# JacdacServoDual_23.net
KiCad netlist of a schematic drawn in Altium Designer
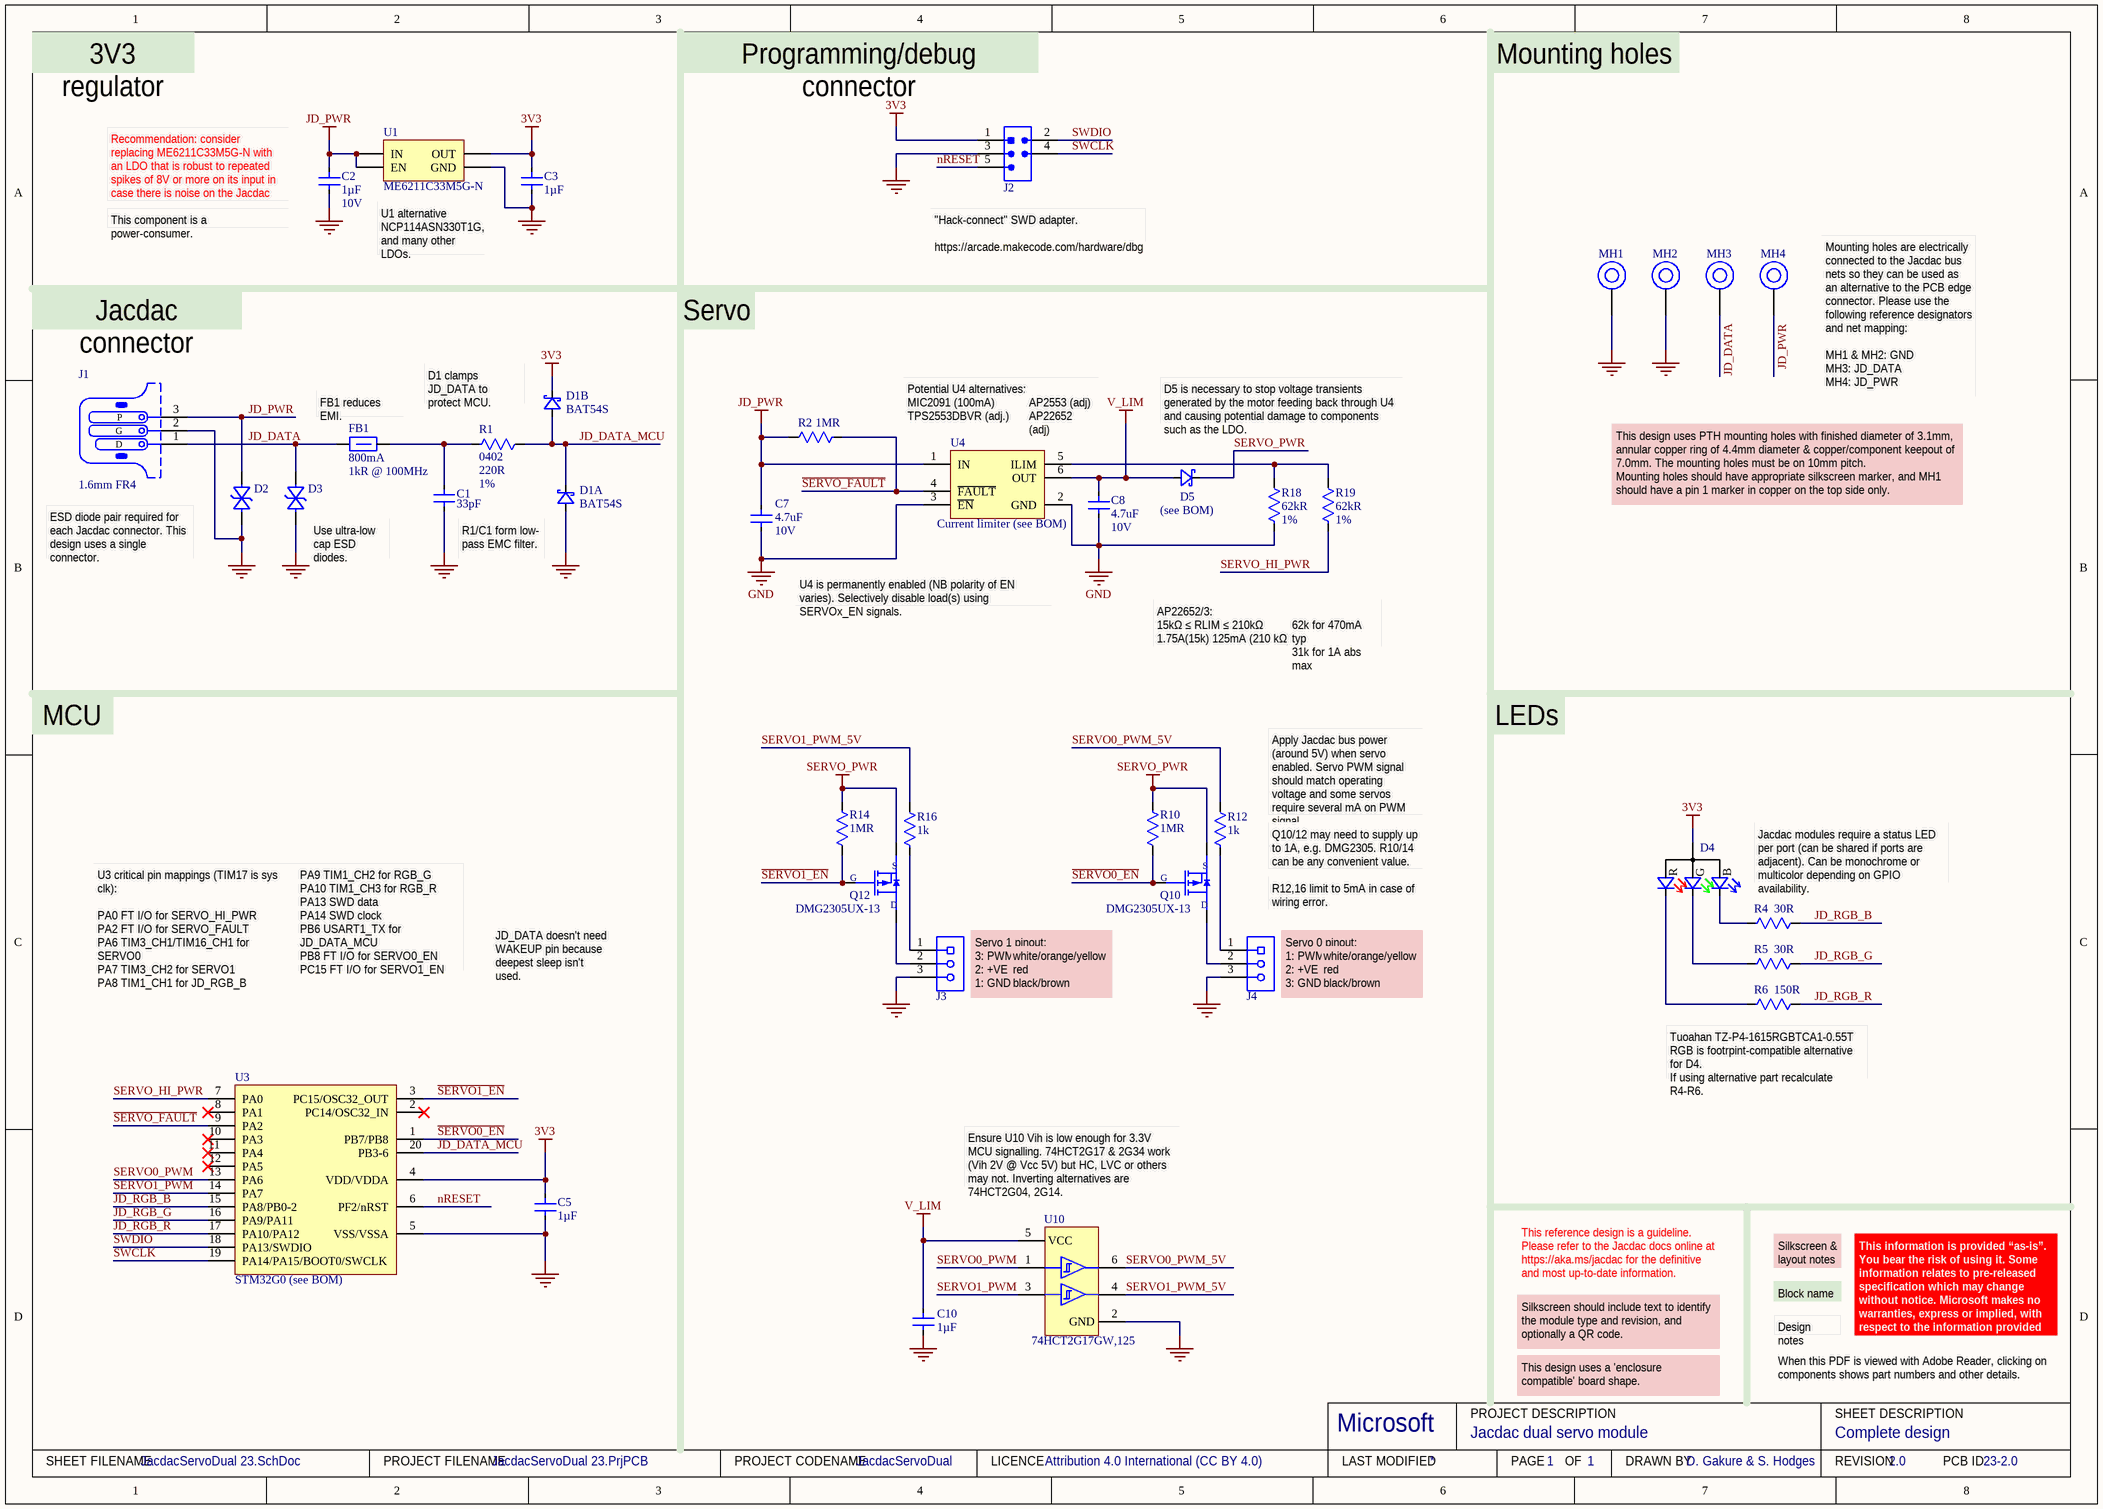
[diagram p0: JacdacServoDual 23.SchDoc]

(export (version "E")
  (design (tool "Eeschema 10.0.6"))
  (components
    (comp (ref "C1")
      (value "CL05C330JB5NNNC")
      (footprint "C0402_0.55MM - without outline")
      (description "CAP CER 33PF 50V C0G/NP0 0402")
      (fields
        (field (name "MANUFACTURER") "Samsung")
        (field (name "TOLERANCE") "5%")
        (field (name "CAPACITANCE") "33pF")
      )
      (libsource (lib "Samsung") (part "CL05C330JB5NNNC"))
    )
    (comp (ref "C2")
      (value "CL05A105KP5NNNC")
      (footprint "C0402_0.55MM - without outline")
      (description "CAP CER 1UF 10V X5R 0402")
      (fields
        (field (name "MANUFACTURER") "Samsung")
        (field (name "TOLERANCE") "10%")
        (field (name "CAPACITANCE") "1µF")
        (field (name "VOLTAGE RATING") "10V")
        (field (name "CREATED") "DG")
        (field (name "CHECKED") "?")
      )
      (libsource (lib "Samsung") (part "CL05A105KP5NNNC"))
    )
    (comp (ref "C3")
      (value "CL05A105KP5NNNC")
      (footprint "C0402_0.55MM - without outline")
      (description "CAP CER 1UF 10V X5R 0402")
      (fields
        (field (name "MANUFACTURER") "Samsung")
        (field (name "TOLERANCE") "10%")
        (field (name "CAPACITANCE") "1µF")
        (field (name "CREATED") "DG")
        (field (name "CHECKED") "?")
      )
      (libsource (lib "Samsung") (part "CL05A105KP5NNNC"))
    )
    (comp (ref "C5")
      (value "CL05A105KP5NNNC")
      (footprint "C0402_0.55MM - without outline")
      (description "CAP CER 1UF 10V X5R 0402")
      (fields
        (field (name "MANUFACTURER") "Samsung")
        (field (name "TOLERANCE") "10%")
        (field (name "CAPACITANCE") "1µF")
        (field (name "CREATED") "DG")
        (field (name "CHECKED") "?")
      )
      (libsource (lib "Samsung") (part "CL05A105KP5NNNC"))
    )
    (comp (ref "C7")
      (value "CL05A475MP5NRNC")
      (footprint "R0402 - Without outline")
      (description "CAP CER 4.7UF 10V X5R 0402")
      (fields
        (field (name "MANUFACTURER") "Samsung")
        (field (name "TOLERANCE") "20%")
        (field (name "CAPACITANCE") "4.7uF")
        (field (name "VOLTAGE RATING") "10V")
        (field (name "CREATED BY") "D. Gakure")
        (field (name "CHECKED BY") "?")
      )
      (libsource (lib "Samsung") (part "CL05A475MP5NRNC"))
    )
    (comp (ref "C8")
      (value "CL05A475MP5NRNC")
      (footprint "R0402 - Without outline")
      (description "CAP CER 4.7UF 10V X5R 0402")
      (fields
        (field (name "MANUFACTURER") "Samsung")
        (field (name "TOLERANCE") "20%")
        (field (name "CAPACITANCE") "4.7uF")
        (field (name "VOLTAGE RATING") "10V")
        (field (name "CREATED BY") "D. Gakure")
        (field (name "CHECKED BY") "?")
      )
      (libsource (lib "Samsung") (part "CL05A475MP5NRNC"))
    )
    (comp (ref "C10")
      (value "CL05A105KP5NNNC")
      (footprint "C0402_0.55MM - without outline")
      (description "CAP CER 1UF 10V X5R 0402")
      (fields
        (field (name "MANUFACTURER") "Samsung")
        (field (name "TOLERANCE") "10%")
        (field (name "CAPACITANCE") "1µF")
        (field (name "CREATED") "DG")
        (field (name "CHECKED") "?")
      )
      (libsource (lib "Samsung") (part "CL05A105KP5NNNC"))
    )
    (comp (ref "D1")
      (value "BAT54S")
      (footprint "NXP-BAT54S-TO-236AB - without outline")
      (description "DIODE ARRAY SCHOTTKY 30V SOT23")
      (fields
        (field (name "MANUFACTURER") "Nexperia")
        (field (name "MANUFACTURER PART NUMBER") "BAT54S,235")
        (field (name "GENERIC PART NUMBER") "BAT54S")
      )
      (libsource (lib "NXP") (part "BAT54S"))
    )
    (comp (ref "D2")
      (value "RCLAMP0521P-N")
      (footprint "TVS 0402 - L")
      (description "Bidirectional 5V (Max) 6V 16V 3.5A (8/20us) 0402 TVS RoHS")
      (fields
        (field (name "MANUFACTURER") "Born Semiconductor")
        (field (name "CREATED BY") "D Gakure")
        (field (name "CHECKED BY") "?")
      )
      (libsource (lib "BornSemiconductor") (part "RCLAMP0521P-N"))
    )
    (comp (ref "D3")
      (value "RCLAMP0521P-N")
      (footprint "TVS 0402 - L")
      (description "Bidirectional 5V (Max) 6V 16V 3.5A (8/20us) 0402 TVS RoHS")
      (fields
        (field (name "MANUFACTURER") "Born Semiconductor")
        (field (name "CREATED BY") "D Gakure")
        (field (name "CHECKED BY") "?")
      )
      (libsource (lib "BornSemiconductor") (part "RCLAMP0521P-N"))
    )
    (comp (ref "D4")
      (value "HSMF-C114")
      (footprint "HSMF-C114")
      (fields
        (field (name "MANUFACTURER") "Broadcom Avago")
        (field (name "CREATED BY") "D. Gakure")
        (field (name "CHECKED BY") "?")
      )
      (libsource (lib "BroadcomLimited") (part "HSMF-C114"))
    )
    (comp (ref "D5")
      (value "MBR120VLSFT3G")
      (footprint "MBR120VLSFT3G")
      (description "DIODE SCHOTTKY 20V 1A SOD123FL")
      (fields
        (field (name "MANUFACTURER") "ON Semiconductor")
        (field (name "GENERIC PART NUMBER") "(see BOM)")
      )
      (libsource (lib "OnSemiconductor") (part "MBR120VLSFT3G"))
    )
    (comp (ref "FB1")
      (value "TDK MPZ1608S102ATA00")
      (footprint "TDK MPZ1608 0.8mm - without outline")
      (description "0603 1k@100MHz 0.8A chip")
      (fields
        (field (name "TOLERANCE") "25%")
        (field (name "MANUFACTURER") "TDK")
        (field (name "CURRENT RATING") "800mA")
        (field (name "IMPEDANCE") "1kR @ 100MHz")
      )
      (libsource (lib "TDK") (part "TDK MPZ1608S102ATA00"))
    )
    (comp (ref "J1")
      (value "3 pin JACDAC edge connector")
      (footprint "JACDAC_EDGE_CONNECTOR_NO_TRACES")
      (description "3 pin Jacdac edge connector 1.27mm pitch")
      (fields
        (field (name "MANUFACTURER PART NUMBER") "JACDAC_EDGE_CONNECTOR")
        (field (name "PCB TYPE") "1.6mm FR4")
        (field (name "CHECKED BY") "?")
        (field (name "CREATED BY") "D. Gakure")
      )
      (libsource (lib "generic-con") (part "Jacdac edge connector"))
    )
    (comp (ref "J2")
      (value "Hack Connect Mini 1.27 mm pitch 2-row")
      (footprint "HACK_CONNECT_MINI_5_X_1_27")
      (libsource (lib "HackConnect") (part "HACK_CONNECT_MINI"))
    )
    (comp (ref "J3")
      (value "TSM-103-01-L-SH-A")
      (footprint "TSM-103-01-L-SH-A")
      (fields (field (name "MANUFACTURER") "Samtec"))
      (libsource (lib "Samtec") (part "TSM-103-01-L-SH-A-whitesch"))
    )
    (comp (ref "J4")
      (value "TSM-103-01-L-SH-A")
      (footprint "TSM-103-01-L-SH-A")
      (fields (field (name "MANUFACTURER") "Samtec"))
      (libsource (lib "Samtec") (part "TSM-103-01-L-SH-A-whitesch"))
    )
    (comp (ref "MH1")
      (value "MH_7.0MMK_4.4MMC_3.1MMD_PTH")
      (footprint "MH_7.0MMK_4.4MMC_3.1MMD_PTH:MH_7.0MMK_4.4MMC_3.1MMD_PTH")
      (description "Mounting Hole 7.0mm keepout, 4.4mm annualar ring and 3.1mm Drill PTH")
      (libsource (lib "generic") (part "MH_7.0MMK_4.4MMC_3.1MMD_PTH"))
    )
    (comp (ref "MH2")
      (value "MH_7.0MMK_4.4MMC_3.1MMD_PTH")
      (footprint "MH_7.0MMK_4.4MMC_3.1MMD_PTH:MH_7.0MMK_4.4MMC_3.1MMD_PTH")
      (description "Mounting Hole 7.0mm keepout, 4.4mm annualar ring and 3.1mm Drill PTH")
      (libsource (lib "generic") (part "MH_7.0MMK_4.4MMC_3.1MMD_PTH"))
    )
    (comp (ref "MH3")
      (value "MH_7.0MMK_4.4MMC_3.1MMD_PTH")
      (footprint "MH_7.0MMK_4.4MMC_3.1MMD_PTH:MH_7.0MMK_4.4MMC_3.1MMD_PTH")
      (description "Mounting Hole 7.0mm keepout, 4.4mm annualar ring and 3.1mm Drill PTH")
      (libsource (lib "generic") (part "MH_7.0MMK_4.4MMC_3.1MMD_PTH"))
    )
    (comp (ref "MH4")
      (value "MH_7.0MMK_4.4MMC_3.1MMD_PTH")
      (footprint "MH_7.0MMK_4.4MMC_3.1MMD_PTH:MH_7.0MMK_4.4MMC_3.1MMD_PTH")
      (description "Mounting Hole 7.0mm keepout, 4.4mm annualar ring and 3.1mm Drill PTH")
      (libsource (lib "generic") (part "MH_7.0MMK_4.4MMC_3.1MMD_PTH"))
    )
    (comp (ref "Q10")
      (value "MOSFET P-CH 20V 4.2A SOT23")
      (footprint "DIODES-SOT23-3")
      (fields (field (name "MANUFACTURER") "Diodes") (field (name "MANUFACTURER PART NUMBER") "DMG2305UX-13"))
      (libsource (lib "DiodesInc") (part "DMG2305UX-whitesch"))
    )
    (comp (ref "Q12")
      (value "MOSFET P-CH 20V 4.2A SOT23")
      (footprint "DIODES-SOT23-3")
      (fields (field (name "MANUFACTURER") "Diodes") (field (name "MANUFACTURER PART NUMBER") "DMG2305UX-13"))
      (libsource (lib "DiodesInc") (part "DMG2305UX-whitesch"))
    )
    (comp (ref "R1")
      (value "RC0402FR-07220RL")
      (footprint "RES0402")
      (description "RES SMD 220 OHM 1% 1/16W 0402")
      (fields
        (field (name "MANUFACTURER") "Yageo")
        (field (name "CASE CODE (IMPERIAL)") "0402")
        (field (name "RESISTANCE") "220R")
        (field (name "TOLERANCE") "1%")
        (field (name "CREATED") "D.G")
        (field (name "CHECKED") "?")
      )
      (libsource (lib "Yageo") (part "RC0402FR-07220RL"))
    )
    (comp (ref "R2")
      (value "RC0402FR-071ML")
      (footprint "R0402 - Without outline")
      (description "RES SMD 1M OHM 1% 1/16W 0402")
      (fields
        (field (name "MANUFACTURER") "Yageo")
        (field (name "RESISTANCE") "1MR")
        (field (name "TOLERANCE") "1%")
        (field (name "CREATED BY") "D. Gakure")
        (field (name "CHECKED BY") "?")
      )
      (libsource (lib "Yageo") (part "RC0402FR-071ML"))
    )
    (comp (ref "R4")
      (value "RC0402FR-0730RL")
      (footprint "R0402 - Without outline")
      (description "RES SMD 30 OHM 1% 1/16W 0402")
      (fields
        (field (name "MANUFACTURER") "Yageo")
        (field (name "RESISTANCE") "30R")
        (field (name "TOLERANCE") "1%")
        (field (name "CREATED BY") "D. Gakure")
        (field (name "CHECKED BY") "?")
      )
      (libsource (lib "Yageo") (part "RC0402FR-0730RL"))
    )
    (comp (ref "R5")
      (value "RC0402FR-0730RL")
      (footprint "R0402 - Without outline")
      (description "RES SMD 30 OHM 1% 1/16W 0402")
      (fields
        (field (name "MANUFACTURER") "Yageo")
        (field (name "RESISTANCE") "30R")
        (field (name "TOLERANCE") "1%")
        (field (name "CREATED BY") "D. Gakure")
        (field (name "CHECKED BY") "?")
      )
      (libsource (lib "Yageo") (part "RC0402FR-0730RL"))
    )
    (comp (ref "R6")
      (value "RC0402FR-07150RL")
      (footprint "R0402 - Without outline")
      (description "RES SMD 150 OHM 1% 1/16W 0402")
      (fields
        (field (name "MANUFACTURER") "Yageo")
        (field (name "RESISTANCE") "150R")
        (field (name "TOLERANCE") "1%")
        (field (name "CREATED BY") "D. Gakure")
        (field (name "CHECKED BY") "?")
      )
      (libsource (lib "Yageo") (part "RC0402FR-07150RL"))
    )
    (comp (ref "R10")
      (value "RC0402FR-071ML")
      (footprint "R0402 - Without outline")
      (description "RES SMD 1M OHM 1% 1/16W 0402")
      (fields
        (field (name "MANUFACTURER") "Yageo")
        (field (name "RESISTANCE") "1MR")
        (field (name "TOLERANCE") "1%")
        (field (name "CREATED BY") "D. Gakure")
        (field (name "CHECKED BY") "?")
      )
      (libsource (lib "Yageo") (part "RC0402FR-071ML"))
    )
    (comp (ref "R12")
      (value "RC0402FR-071KL")
      (footprint "RES0402")
      (description "RES SMD 1K OHM 1% 1/16W 0402")
      (fields
        (field (name "MANUFACTURER") "Yageo")
        (field (name "TOLERANCE") "1%")
        (field (name "RESISTANCE") "1k")
        (field (name "CREATED") "D.G")
        (field (name "CHECKED") "?")
      )
      (libsource (lib "Yageo") (part "RC0402FR-071KL"))
    )
    (comp (ref "R14")
      (value "RC0402FR-071ML")
      (footprint "R0402 - Without outline")
      (description "RES SMD 1M OHM 1% 1/16W 0402")
      (fields
        (field (name "MANUFACTURER") "Yageo")
        (field (name "RESISTANCE") "1MR")
        (field (name "TOLERANCE") "1%")
        (field (name "CREATED BY") "D. Gakure")
        (field (name "CHECKED BY") "?")
      )
      (libsource (lib "Yageo") (part "RC0402FR-071ML"))
    )
    (comp (ref "R16")
      (value "RC0402FR-071KL")
      (footprint "RES0402")
      (description "RES SMD 1K OHM 1% 1/16W 0402")
      (fields
        (field (name "MANUFACTURER") "Yageo")
        (field (name "TOLERANCE") "1%")
        (field (name "RESISTANCE") "1k")
        (field (name "CREATED") "D.G")
        (field (name "CHECKED") "?")
      )
      (libsource (lib "Yageo") (part "RC0402FR-071KL"))
    )
    (comp (ref "R18")
      (value "RC0402FR-0762KL")
      (footprint "R0402 - Without outline")
      (description "RES SMD 62K OHM 1% 1/16W 0402")
      (fields (field (name "RESISTANCE") "62kR") (field (name "TOLERANCE") "1%"))
      (libsource (lib "Yageo") (part "RC0402FR-0762KL"))
    )
    (comp (ref "R19")
      (value "RC0402FR-0762KL")
      (footprint "R0402 - Without outline")
      (description "RES SMD 62K OHM 1% 1/16W 0402")
      (fields (field (name "RESISTANCE") "62kR") (field (name "TOLERANCE") "1%"))
      (libsource (lib "Yageo") (part "RC0402FR-0762KL"))
    )
    (comp (ref "U1")
      (value "ME6211C33M5G-N")
      (footprint "MICRONE-SOT23-5")
      (description "6V 260mV @ 200mA(typ) - - Fixed 3.3V SOT-23-5 Linear Voltage Regulators (LDO) ROHS")
      (fields
        (field (name "MANUFACTURER") "MICRONE(Nanjing Micro One Elec)")
        (field (name "MANUFACTURER PART NUMBER") "ME6211C33M5G-N")
        (field (name "CREATED") "DG")
        (field (name "CHECKED") "?")
      )
      (libsource (lib "MICRONE(NanjingMicroOneElec)") (part "ME6211C33M5G-N"))
    )
    (comp (ref "U3")
      (value "~")
      (footprint "20-TSSOP")
      (description "MCU 32-Bit STM32G031 ARM Cortex-M0+ RISC 32KB Flash 1.7V to 3.6V 20-Pin TSSOP Tube")
      (fields
        (field (name "MANUFACTURER") "STMicroelectronics")
        (field (name "MANUFACTURER PART NUMBER") "STM32G031F6P6")
        (field (name "GENERIC PART NUMBER") "STM32G0 (see BOM)")
        (field (name "CREATED BY") "D. Gakure")
        (field (name "CHECKED BY") "?")
      )
      (libsource (lib "ST") (part "STM32G031F6P6"))
    )
    (comp (ref "U4")
      (value "AP22652W6-7")
      (footprint "SOT-26")
      (description "USB Power High Side Switch Single 3V to 5.5V 2.1A 6-Pin SOT-26 T/R")
      (fields (field (name "GENERIC PART NUMBER") "Current limiter (see BOM)"))
      (libsource (lib "DiodesInc") (part "AP22652W6-7"))
    )
    (comp (ref "U10")
      (value "74HCT2G17GW,125")
      (footprint "NXP-TSSOP-6:6TSSOP_SOT457")
      (description "74HCT2G17 Series 5.5 V 4 mA Dual Non-Inverting Schmitt Trigger - TSSOP-6")
      (fields (field (name "MANUFACTURER PART NUMBER 1") "74HCT2G17GW,125"))
      (libsource (lib "Nexperia") (part "74HCT2G17GW,125"))
    )
  )
  (nets
    (net (code "1") (name "/JD_DATA") (class "Default")
      (node (ref "D3") (pin "1") (pinfunction "K_1") (pintype "passive"))
      (node (ref "FB1") (pin "1") (pinfunction "1_1") (pintype "passive"))
      (node (ref "J1") (pin "1") (pinfunction "D_1") (pintype "passive"))
      (node (ref "MH3") (pin "1") (pinfunction "1_1") (pintype "passive"))
    )
    (net (code "2") (name "/JD_DATA_MCU") (class "Default")
      (node (ref "D1") (pin "3") (pinfunction "K_3") (pintype "passive"))
      (node (ref "R1") (pin "1") (pinfunction "1_1") (pintype "passive"))
      (node (ref "U3") (pin "20") (pinfunction "PB3-6_20") (pintype "power_in"))
    )
    (net (code "3") (name "/JD_RGB_B") (class "Default")
      (node (ref "R4") (pin "2") (pinfunction "2_2") (pintype "passive"))
      (node (ref "U3") (pin "15") (pinfunction "PA8/PB0-2_15") (pintype "passive"))
    )
    (net (code "4") (name "/JD_RGB_G") (class "Default")
      (node (ref "R5") (pin "2") (pinfunction "2_2") (pintype "passive"))
      (node (ref "U3") (pin "16") (pinfunction "PA9/PA11_16") (pintype "passive"))
    )
    (net (code "5") (name "/JD_RGB_R") (class "Default")
      (node (ref "R6") (pin "2") (pinfunction "2_2") (pintype "passive"))
      (node (ref "U3") (pin "17") (pinfunction "PA10/PA12_17") (pintype "passive"))
    )
    (net (code "6") (name "/SERVO0_PWM") (class "Default")
      (node (ref "U10") (pin "1") (pinfunction "1A_1") (pintype "passive"))
      (node (ref "U3") (pin "13") (pinfunction "PA6_13") (pintype "passive"))
    )
    (net (code "7") (name "/SERVO0_PWM_5V") (class "Default")
      (node (ref "R12") (pin "1") (pinfunction "1_1") (pintype "passive"))
      (node (ref "U10") (pin "6") (pinfunction "1Y_6") (pintype "passive"))
    )
    (net (code "8") (name "/SERVO1_PWM") (class "Default")
      (node (ref "U10") (pin "3") (pinfunction "2A_3") (pintype "passive"))
      (node (ref "U3") (pin "14") (pinfunction "PA7_14") (pintype "passive"))
    )
    (net (code "9") (name "/SERVO1_PWM_5V") (class "Default")
      (node (ref "R16") (pin "1") (pinfunction "1_1") (pintype "passive"))
      (node (ref "U10") (pin "4") (pinfunction "2Y_4") (pintype "passive"))
    )
    (net (code "10") (name "/SERVO_HI_PWR") (class "Default")
      (node (ref "R19") (pin "1") (pinfunction "1_1") (pintype "passive"))
      (node (ref "U3") (pin "7") (pinfunction "PA0_7") (pintype "passive"))
    )
    (net (code "11") (name "/SWCLK") (class "Default")
      (node (ref "J2") (pin "4") (pinfunction "SWCLK_4") (pintype "passive"))
      (node (ref "U3") (pin "19") (pinfunction "PA14/PA15/BOOT0/SWCLK_19") (pintype "passive"))
    )
    (net (code "12") (name "/SWDIO") (class "Default")
      (node (ref "J2") (pin "2") (pinfunction "SWDIO_2") (pintype "passive"))
      (node (ref "U3") (pin "18") (pinfunction "PA13/SWDIO_18") (pintype "passive"))
    )
    (net (code "13") (name "/nRESET") (class "Default")
      (node (ref "J2") (pin "5") (pinfunction "RESET_5") (pintype "passive"))
      (node (ref "U3") (pin "6") (pinfunction "PF2/nRST_6") (pintype "power_in"))
    )
    (net (code "14") (name "/~{SERVO0_EN}") (class "Default")
      (node (ref "Q10") (pin "1") (pinfunction "G_1") (pintype "passive"))
      (node (ref "R10") (pin "1") (pinfunction "1_1") (pintype "passive"))
      (node (ref "U3") (pin "1") (pinfunction "PB7/PB8_1") (pintype "passive"))
    )
    (net (code "15") (name "/~{SERVO1_EN}") (class "Default")
      (node (ref "Q12") (pin "1") (pinfunction "G_1") (pintype "passive"))
      (node (ref "R14") (pin "1") (pinfunction "1_1") (pintype "passive"))
      (node (ref "U3") (pin "3") (pinfunction "PC15/OSC32_OUT_3") (pintype "passive"))
    )
    (net (code "16") (name "/~{SERVO_FAULT}") (class "Default")
      (node (ref "R2") (pin "2") (pinfunction "2_2") (pintype "passive"))
      (node (ref "U3") (pin "9") (pinfunction "PA2_9") (pintype "passive"))
      (node (ref "U4") (pin "4") (pinfunction "~{FAULT}_4") (pintype "passive"))
    )
    (net (code "17") (name "3V3") (class "Default")
      (node (ref "C3") (pin "2") (pinfunction "2_2") (pintype "passive"))
      (node (ref "C5") (pin "2") (pinfunction "2_2") (pintype "passive"))
      (node (ref "D1") (pin "2") (pinfunction "K_2") (pintype "passive"))
      (node (ref "D4") (pin "1") (pinfunction "A_1") (pintype "passive"))
      (node (ref "J2") (pin "1") (pinfunction "VCC_1") (pintype "passive"))
      (node (ref "U1") (pin "5") (pinfunction "OUT_5") (pintype "passive"))
      (node (ref "U3") (pin "4") (pinfunction "VDD/VDDA_4") (pintype "passive"))
    )
    (net (code "18") (name "GND") (class "Default")
      (node (ref "C1") (pin "1") (pinfunction "1_1") (pintype "passive"))
      (node (ref "C10") (pin "1") (pinfunction "1_1") (pintype "passive"))
      (node (ref "C2") (pin "1") (pinfunction "1_1") (pintype "passive"))
      (node (ref "C3") (pin "1") (pinfunction "1_1") (pintype "passive"))
      (node (ref "C5") (pin "1") (pinfunction "1_1") (pintype "passive"))
      (node (ref "C7") (pin "1") (pinfunction "1_1") (pintype "passive"))
      (node (ref "C8") (pin "1") (pinfunction "1_1") (pintype "passive"))
      (node (ref "D1") (pin "1") (pinfunction "A_1") (pintype "passive"))
      (node (ref "D2") (pin "2") (pinfunction "A_2") (pintype "passive"))
      (node (ref "D3") (pin "2") (pinfunction "A_2") (pintype "passive"))
      (node (ref "J1") (pin "2") (pinfunction "G_2") (pintype "passive"))
      (node (ref "J2") (pin "3") (pinfunction "GND_3") (pintype "passive"))
      (node (ref "J3") (pin "3") (pinfunction "3_3") (pintype "passive"))
      (node (ref "J4") (pin "3") (pinfunction "3_3") (pintype "passive"))
      (node (ref "MH1") (pin "1") (pinfunction "1_1") (pintype "passive"))
      (node (ref "MH2") (pin "1") (pinfunction "1_1") (pintype "passive"))
      (node (ref "R18") (pin "1") (pinfunction "1_1") (pintype "passive"))
      (node (ref "U1") (pin "2") (pinfunction "GND_2") (pintype "passive"))
      (node (ref "U10") (pin "2") (pinfunction "GND_2") (pintype "passive"))
      (node (ref "U3") (pin "5") (pinfunction "VSS/VSSA_5") (pintype "power_in"))
      (node (ref "U4") (pin "2") (pinfunction "GND_2") (pintype "passive"))
      (node (ref "U4") (pin "3") (pinfunction "~{EN}_3") (pintype "passive"))
    )
    (net (code "19") (name "JD_PWR") (class "Default")
      (node (ref "C2") (pin "2") (pinfunction "2_2") (pintype "passive"))
      (node (ref "C7") (pin "2") (pinfunction "2_2") (pintype "passive"))
      (node (ref "D2") (pin "1") (pinfunction "K_1") (pintype "passive"))
      (node (ref "J1") (pin "3") (pinfunction "P_3") (pintype "passive"))
      (node (ref "MH4") (pin "1") (pinfunction "1_1") (pintype "passive"))
      (node (ref "R2") (pin "1") (pinfunction "1_1") (pintype "passive"))
      (node (ref "U1") (pin "1") (pinfunction "IN_1") (pintype "passive"))
      (node (ref "U1") (pin "3") (pinfunction "EN_3") (pintype "passive"))
      (node (ref "U4") (pin "1") (pinfunction "IN_1") (pintype "passive"))
    )
    (net (code "20") (name "Net-(C1-Pad2)") (class "Default")
      (node (ref "C1") (pin "2") (pinfunction "2_2") (pintype "passive"))
      (node (ref "FB1") (pin "2") (pinfunction "2_2") (pintype "passive"))
      (node (ref "R1") (pin "2") (pinfunction "2_2") (pintype "passive"))
    )
    (net (code "21") (name "Net-(D4-B)") (class "Default")
      (node (ref "D4") (pin "4") (pinfunction "B_4") (pintype "passive"))
      (node (ref "R4") (pin "1") (pinfunction "1_1") (pintype "passive"))
    )
    (net (code "22") (name "Net-(D4-G)") (class "Default")
      (node (ref "D4") (pin "3") (pinfunction "G_3") (pintype "passive"))
      (node (ref "R5") (pin "1") (pinfunction "1_1") (pintype "passive"))
    )
    (net (code "23") (name "Net-(D4-R)") (class "Default")
      (node (ref "D4") (pin "2") (pinfunction "R_2") (pintype "passive"))
      (node (ref "R6") (pin "1") (pinfunction "1_1") (pintype "passive"))
    )
    (net (code "24") (name "Net-(J3-Pad1)") (class "Default")
      (node (ref "J3") (pin "1") (pinfunction "1_1") (pintype "passive"))
      (node (ref "R16") (pin "2") (pinfunction "2_2") (pintype "passive"))
    )
    (net (code "25") (name "Net-(J4-Pad1)") (class "Default")
      (node (ref "J4") (pin "1") (pinfunction "1_1") (pintype "passive"))
      (node (ref "R12") (pin "2") (pinfunction "2_2") (pintype "passive"))
    )
    (net (code "26") (name "Net-(Q10-D)") (class "Default")
      (node (ref "J4") (pin "2") (pinfunction "2_2") (pintype "passive"))
      (node (ref "Q10") (pin "3") (pinfunction "D_3") (pintype "passive"))
    )
    (net (code "27") (name "Net-(Q12-D)") (class "Default")
      (node (ref "J3") (pin "2") (pinfunction "2_2") (pintype "passive"))
      (node (ref "Q12") (pin "3") (pinfunction "D_3") (pintype "passive"))
    )
    (net (code "28") (name "Net-(U4-ILIM)") (class "Default")
      (node (ref "R18") (pin "2") (pinfunction "2_2") (pintype "passive"))
      (node (ref "R19") (pin "2") (pinfunction "2_2") (pintype "passive"))
      (node (ref "U4") (pin "5") (pinfunction "ILIM_5") (pintype "passive"))
    )
    (net (code "29") (name "SERVO_PWR") (class "Default")
      (node (ref "D5") (pin "1") (pinfunction "K_1") (pintype "passive"))
      (node (ref "Q10") (pin "2") (pinfunction "S_2") (pintype "passive"))
      (node (ref "Q12") (pin "2") (pinfunction "S_2") (pintype "passive"))
      (node (ref "R10") (pin "2") (pinfunction "2_2") (pintype "passive"))
      (node (ref "R14") (pin "2") (pinfunction "2_2") (pintype "passive"))
    )
    (net (code "30") (name "V_LIM") (class "Default")
      (node (ref "C10") (pin "2") (pinfunction "2_2") (pintype "passive"))
      (node (ref "C8") (pin "2") (pinfunction "2_2") (pintype "passive"))
      (node (ref "D5") (pin "2") (pinfunction "A_2") (pintype "passive"))
      (node (ref "U10") (pin "5") (pinfunction "VCC_5") (pintype "passive"))
      (node (ref "U4") (pin "6") (pinfunction "OUT_6") (pintype "passive"))
    )
    (net (code "31") (name "unconnected-(U3-PA1-Pad8)") (class "Default")
      (node (ref "U3") (pin "8") (pinfunction "PA1_8") (pintype "passive+no_connect"))
    )
    (net (code "32") (name "unconnected-(U3-PA3-Pad10)") (class "Default")
      (node (ref "U3") (pin "10") (pinfunction "PA3_10") (pintype "passive+no_connect"))
    )
    (net (code "33") (name "unconnected-(U3-PA4-Pad11)") (class "Default")
      (node (ref "U3") (pin "11") (pinfunction "PA4_11") (pintype "passive+no_connect"))
    )
    (net (code "34") (name "unconnected-(U3-PA5-Pad12)") (class "Default")
      (node (ref "U3") (pin "12") (pinfunction "PA5_12") (pintype "passive+no_connect"))
    )
    (net (code "35") (name "unconnected-(U3-PC14{slash}OSC32_IN-Pad2)") (class "Default")
      (node (ref "U3") (pin "2") (pinfunction "PC14/OSC32_IN_2") (pintype "passive+no_connect"))
    )
  )
)
